# IRQF401RCT6.net
KiCad netlist of a schematic drawn in EAGLE
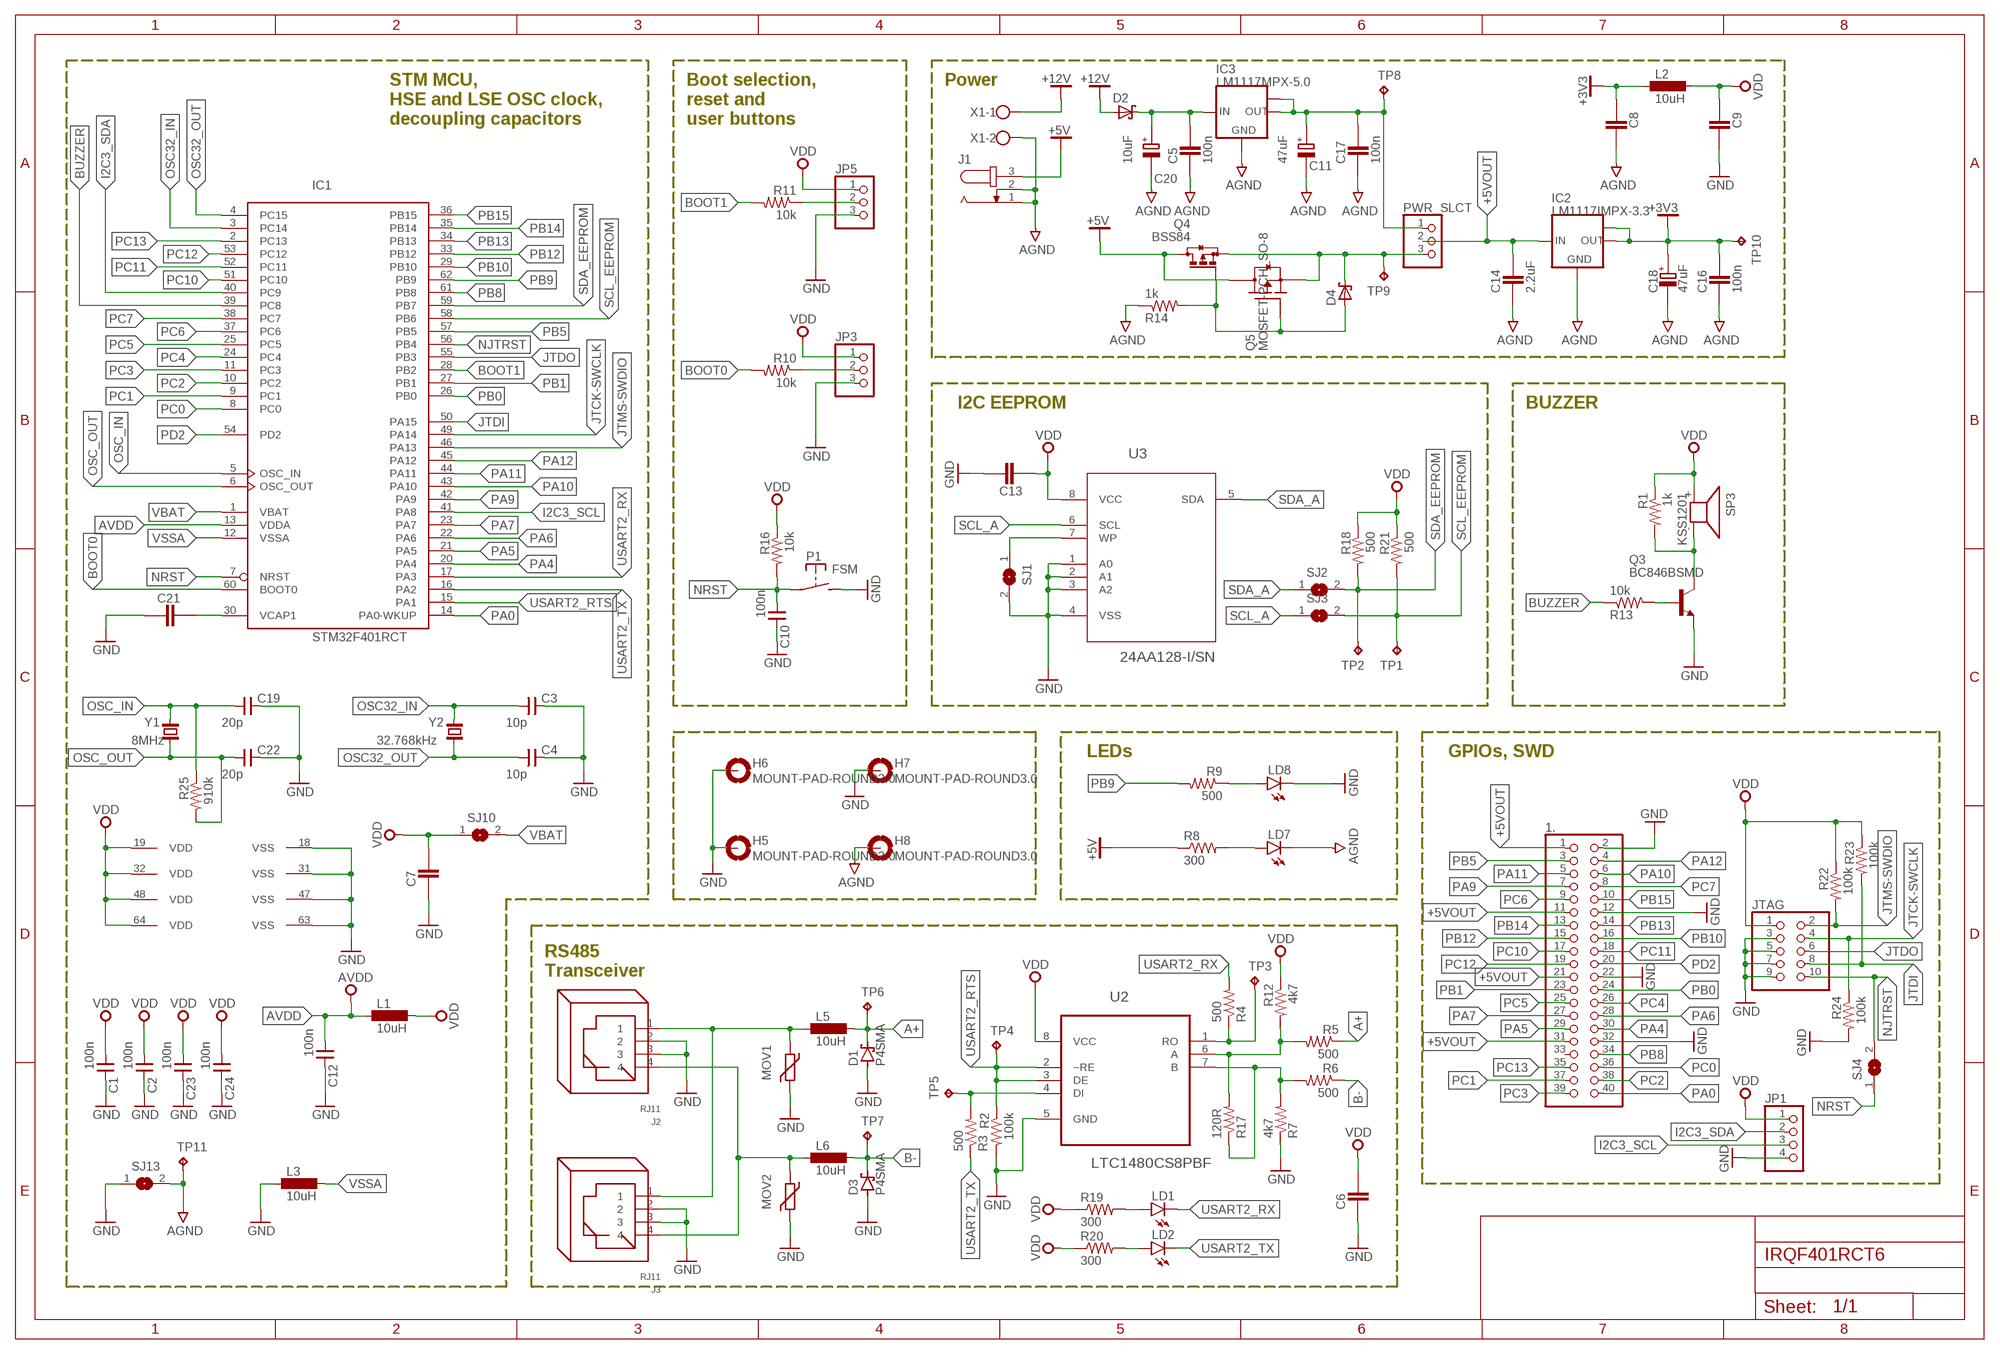
[diagram p0: schematic, sheet 1]

(export (version "E")
  (design (tool "Eeschema 10.0.6"))
  (components
    (comp (ref "1.")
      (value "PINHD-2X20")
      (footprint "eagle-import:2X20")
      (libsource (lib "eagle-import") (part "PINHD-2X20"))
    )
    (comp (ref "C1")
      (value "100n")
      (footprint "eagle-import:0805")
      (libsource (lib "eagle-import") (part "CNP-0805"))
    )
    (comp (ref "C2")
      (value "100n")
      (footprint "eagle-import:0805")
      (libsource (lib "eagle-import") (part "CNP-0805"))
    )
    (comp (ref "C3")
      (value "10p")
      (footprint "eagle-import:0805")
      (libsource (lib "eagle-import") (part "CNP-0805"))
    )
    (comp (ref "C4")
      (value "10p")
      (footprint "eagle-import:0805")
      (libsource (lib "eagle-import") (part "CNP-0805"))
    )
    (comp (ref "C5")
      (value "100n")
      (footprint "eagle-import:CAPC2012X145AN")
      (libsource (lib "eagle-import") (part "CAPACITOR_0805"))
    )
    (comp (ref "C6")
      (value "CAPACITOR_1206")
      (footprint "eagle-import:CAPC3215X168N")
      (libsource (lib "eagle-import") (part "CAPACITOR_1206"))
    )
    (comp (ref "C7")
      (value "CAPACITOR_1206")
      (footprint "eagle-import:CAPC3215X168N")
      (libsource (lib "eagle-import") (part "CAPACITOR_1206"))
    )
    (comp (ref "C8")
      (value "CAPACITOR_1206")
      (footprint "eagle-import:CAPC3215X168N")
      (libsource (lib "eagle-import") (part "CAPACITOR_1206"))
    )
    (comp (ref "C9")
      (value "CAPACITOR_1206")
      (footprint "eagle-import:CAPC3215X168N")
      (libsource (lib "eagle-import") (part "CAPACITOR_1206"))
    )
    (comp (ref "C10")
      (value "100n")
      (footprint "eagle-import:0805")
      (libsource (lib "eagle-import") (part "CNP-0805"))
    )
    (comp (ref "C11")
      (value "47uF")
      (footprint "eagle-import:CAPAE660X540N")
      (libsource (lib "eagle-import") (part "POLARISED_CASE_D"))
    )
    (comp (ref "C12")
      (value "100n")
      (footprint "eagle-import:0805")
      (libsource (lib "eagle-import") (part "CNP-0805"))
    )
    (comp (ref "C13")
      (value "CAPACITOR_1206")
      (footprint "eagle-import:CAPC3215X168N")
      (libsource (lib "eagle-import") (part "CAPACITOR_1206"))
    )
    (comp (ref "C14")
      (value "2.2uF")
      (footprint "eagle-import:CAPC3215X168N")
      (libsource (lib "eagle-import") (part "CAPACITOR_1206"))
    )
    (comp (ref "C16")
      (value "100n")
      (footprint "eagle-import:CAPC2012X145AN")
      (libsource (lib "eagle-import") (part "CAPACITOR_0805"))
    )
    (comp (ref "C17")
      (value "100n")
      (footprint "eagle-import:CAPC2012X145AN")
      (libsource (lib "eagle-import") (part "CAPACITOR_0805"))
    )
    (comp (ref "C18")
      (value "47uF")
      (footprint "eagle-import:CAPAE530X540N")
      (libsource (lib "eagle-import") (part "POLARISED_CASE_C"))
    )
    (comp (ref "C19")
      (value "20p")
      (footprint "eagle-import:0805")
      (libsource (lib "eagle-import") (part "CNP-0805"))
    )
    (comp (ref "C20")
      (value "10uF")
      (footprint "eagle-import:CAPAE430X540N")
      (libsource (lib "eagle-import") (part "POLARISED_CASE_B"))
    )
    (comp (ref "C21")
      (value "CAPACITOR_1206")
      (footprint "eagle-import:CAPC3215X168N")
      (libsource (lib "eagle-import") (part "CAPACITOR_1206"))
    )
    (comp (ref "C22")
      (value "20p")
      (footprint "eagle-import:0805")
      (libsource (lib "eagle-import") (part "CNP-0805"))
    )
    (comp (ref "C23")
      (value "100n")
      (footprint "eagle-import:0805")
      (libsource (lib "eagle-import") (part "CNP-0805"))
    )
    (comp (ref "C24")
      (value "100n")
      (footprint "eagle-import:0805")
      (libsource (lib "eagle-import") (part "CNP-0805"))
    )
    (comp (ref "D1")
      (value "P4SMA")
      (footprint "eagle-import:SMB")
      (libsource (lib "eagle-import") (part "SCHOTTKY-DIODESMD"))
    )
    (comp (ref "D2")
      (value "SCHOTTKY_SMA")
      (footprint "eagle-import:DIOM5326X292N")
      (libsource (lib "eagle-import") (part "SCHOTTKY_SMA"))
    )
    (comp (ref "D3")
      (value "P4SMA")
      (footprint "eagle-import:SMB")
      (libsource (lib "eagle-import") (part "SCHOTTKY-DIODESMD"))
    )
    (comp (ref "D4")
      (value "SCHOTTKY_SMA")
      (footprint "eagle-import:DIOM5326X292N")
      (libsource (lib "eagle-import") (part "SCHOTTKY_SMA"))
    )
    (comp (ref "H5")
      (value "MOUNT-PAD-ROUND3.0")
      (footprint "eagle-import:3,0-PAD")
      (libsource (lib "eagle-import") (part "MOUNT-PAD-ROUND3.0"))
    )
    (comp (ref "H6")
      (value "MOUNT-PAD-ROUND3.0")
      (footprint "eagle-import:3,0-PAD")
      (libsource (lib "eagle-import") (part "MOUNT-PAD-ROUND3.0"))
    )
    (comp (ref "H7")
      (value "MOUNT-PAD-ROUND3.0")
      (footprint "eagle-import:3,0-PAD")
      (libsource (lib "eagle-import") (part "MOUNT-PAD-ROUND3.0"))
    )
    (comp (ref "H8")
      (value "MOUNT-PAD-ROUND3.0")
      (footprint "eagle-import:3,0-PAD")
      (libsource (lib "eagle-import") (part "MOUNT-PAD-ROUND3.0"))
    )
    (comp (ref "IC1")
      (value "STM32F401RCT")
      (footprint "eagle-import:LQFP64")
      (libsource (lib "eagle-import") (part "STM32F401RTC"))
    )
    (comp (ref "IC2")
      (value "LM1117IMPX-3.3")
      (footprint "eagle-import:SOT223")
      (libsource (lib "eagle-import") (part "LM1117IMPX-3.3"))
    )
    (comp (ref "IC3")
      (value "LM1117MPX-5.0")
      (footprint "eagle-import:SOT223")
      (libsource (lib "eagle-import") (part "LM1117MPX-5.0"))
    )
    (comp (ref "J1")
      (value "JACK-PLUG1")
      (footprint "eagle-import:SPC4078")
      (libsource (lib "eagle-import") (part "JACK-PLUG1"))
    )
    (comp (ref "J2")
      (value "RJ11")
      (footprint "eagle-import:RJ11")
      (libsource (lib "eagle-import") (part "RJ11"))
    )
    (comp (ref "J3")
      (value "RJ11")
      (footprint "eagle-import:RJ11")
      (libsource (lib "eagle-import") (part "RJ11"))
    )
    (comp (ref "JP1")
      (value "PINHD-1X4")
      (footprint "eagle-import:1X04")
      (libsource (lib "eagle-import") (part "PINHD-1X4"))
    )
    (comp (ref "JP3")
      (value "PINHD-1X3")
      (footprint "eagle-import:1X03")
      (libsource (lib "eagle-import") (part "PINHD-1X3"))
    )
    (comp (ref "JP5")
      (value "PINHD-1X3")
      (footprint "eagle-import:1X03")
      (libsource (lib "eagle-import") (part "PINHD-1X3"))
    )
    (comp (ref "JTAG")
      (value "PINHD-2X5")
      (footprint "eagle-import:2X05")
      (libsource (lib "eagle-import") (part "PINHD-2X5"))
    )
    (comp (ref "L1")
      (value "10uH")
      (footprint "eagle-import:INDC1608X95N")
      (libsource (lib "eagle-import") (part "INDUCTOR_0603"))
    )
    (comp (ref "L2")
      (value "10uH")
      (footprint "eagle-import:INDC1608X95N")
      (libsource (lib "eagle-import") (part "INDUCTOR_0603"))
    )
    (comp (ref "L3")
      (value "10uH")
      (footprint "eagle-import:INDC1608X95N")
      (libsource (lib "eagle-import") (part "INDUCTOR_0603"))
    )
    (comp (ref "L5")
      (value "10uH")
      (footprint "eagle-import:INDC1608X95N")
      (libsource (lib "eagle-import") (part "INDUCTOR_0603"))
    )
    (comp (ref "L6")
      (value "10uH")
      (footprint "eagle-import:INDC1608X95N")
      (libsource (lib "eagle-import") (part "INDUCTOR_0603"))
    )
    (comp (ref "LD1")
      (value "LEDCHIPLED_0805")
      (footprint "eagle-import:CHIPLED_0805")
      (libsource (lib "eagle-import") (part "LEDCHIPLED_0805"))
    )
    (comp (ref "LD2")
      (value "LEDCHIPLED_0805")
      (footprint "eagle-import:CHIPLED_0805")
      (libsource (lib "eagle-import") (part "LEDCHIPLED_0805"))
    )
    (comp (ref "LD7")
      (value "LEDCHIPLED_0805")
      (footprint "eagle-import:CHIPLED_0805")
      (libsource (lib "eagle-import") (part "LEDCHIPLED_0805"))
    )
    (comp (ref "LD8")
      (value "LEDCHIPLED_0805")
      (footprint "eagle-import:CHIPLED_0805")
      (libsource (lib "eagle-import") (part "LEDCHIPLED_0805"))
    )
    (comp (ref "MOV1")
      (value "VARISTOR_0805")
      (footprint "eagle-import:VARC2012X70N")
      (libsource (lib "eagle-import") (part "VARISTOR_0805"))
    )
    (comp (ref "MOV2")
      (value "VARISTOR_0805")
      (footprint "eagle-import:VARC2012X70N")
      (libsource (lib "eagle-import") (part "VARISTOR_0805"))
    )
    (comp (ref "P1")
      (value "FSM")
      (footprint "eagle-import:FSM")
      (libsource (lib "eagle-import") (part "FSM"))
    )
    (comp (ref "PWR_SLCT")
      (value "PINHD-1X3")
      (footprint "eagle-import:1X03")
      (libsource (lib "eagle-import") (part "PINHD-1X3"))
    )
    (comp (ref "Q3")
      (value "BC846BSMD")
      (footprint "eagle-import:SOT23")
      (libsource (lib "eagle-import") (part "BC846SMDB"))
    )
    (comp (ref "Q4")
      (value "BSS84")
      (footprint "eagle-import:SOT23")
      (libsource (lib "eagle-import") (part "BSS84"))
    )
    (comp (ref "Q5")
      (value "MOSFET-PCH_SO-8")
      (footprint "eagle-import:SOIC127P600X175-8AN")
      (libsource (lib "eagle-import") (part "MOSFET-PCH_SO-8"))
    )
    (comp (ref "R1")
      (value "1k")
      (footprint "eagle-import:M0805")
      (libsource (lib "eagle-import") (part "R-US_M0805"))
    )
    (comp (ref "R2")
      (value "100k")
      (footprint "eagle-import:M0805")
      (libsource (lib "eagle-import") (part "R-US_M0805"))
    )
    (comp (ref "R3")
      (value "500")
      (footprint "eagle-import:M0805")
      (libsource (lib "eagle-import") (part "R-US_M0805"))
    )
    (comp (ref "R4")
      (value "500")
      (footprint "eagle-import:M0805")
      (libsource (lib "eagle-import") (part "R-US_M0805"))
    )
    (comp (ref "R5")
      (value "500")
      (footprint "eagle-import:M0805")
      (libsource (lib "eagle-import") (part "R-US_M0805"))
    )
    (comp (ref "R6")
      (value "500")
      (footprint "eagle-import:M0805")
      (libsource (lib "eagle-import") (part "R-US_M0805"))
    )
    (comp (ref "R7")
      (value "4k7")
      (footprint "eagle-import:M0805")
      (libsource (lib "eagle-import") (part "R-US_M0805"))
    )
    (comp (ref "R8")
      (value "300")
      (footprint "eagle-import:M0805")
      (libsource (lib "eagle-import") (part "R-US_M0805"))
    )
    (comp (ref "R9")
      (value "500")
      (footprint "eagle-import:M0805")
      (libsource (lib "eagle-import") (part "R-US_M0805"))
    )
    (comp (ref "R10")
      (value "10k")
      (footprint "eagle-import:M0805")
      (libsource (lib "eagle-import") (part "R-US_M0805"))
    )
    (comp (ref "R11")
      (value "10k")
      (footprint "eagle-import:M0805")
      (libsource (lib "eagle-import") (part "R-US_M0805"))
    )
    (comp (ref "R12")
      (value "4k7")
      (footprint "eagle-import:M0805")
      (libsource (lib "eagle-import") (part "R-US_M0805"))
    )
    (comp (ref "R13")
      (value "10k")
      (footprint "eagle-import:M0805")
      (libsource (lib "eagle-import") (part "R-US_M0805"))
    )
    (comp (ref "R14")
      (value "1k")
      (footprint "eagle-import:M0805")
      (libsource (lib "eagle-import") (part "R-US_M0805"))
    )
    (comp (ref "R16")
      (value "10k")
      (footprint "eagle-import:M0805")
      (libsource (lib "eagle-import") (part "R-US_M0805"))
    )
    (comp (ref "R17")
      (value "120R")
      (footprint "eagle-import:M0805")
      (libsource (lib "eagle-import") (part "R-US_M0805"))
    )
    (comp (ref "R18")
      (value "500")
      (footprint "eagle-import:M0805")
      (libsource (lib "eagle-import") (part "R-US_M0805"))
    )
    (comp (ref "R19")
      (value "300")
      (footprint "eagle-import:M0805")
      (libsource (lib "eagle-import") (part "R-US_M0805"))
    )
    (comp (ref "R20")
      (value "300")
      (footprint "eagle-import:M0805")
      (libsource (lib "eagle-import") (part "R-US_M0805"))
    )
    (comp (ref "R21")
      (value "500")
      (footprint "eagle-import:M0805")
      (libsource (lib "eagle-import") (part "R-US_M0805"))
    )
    (comp (ref "R22")
      (value "100k")
      (footprint "eagle-import:M0805")
      (libsource (lib "eagle-import") (part "R-US_M0805"))
    )
    (comp (ref "R23")
      (value "100k")
      (footprint "eagle-import:M0805")
      (libsource (lib "eagle-import") (part "R-US_M0805"))
    )
    (comp (ref "R24")
      (value "100k")
      (footprint "eagle-import:M0805")
      (libsource (lib "eagle-import") (part "R-US_M0805"))
    )
    (comp (ref "R25")
      (value "910k")
      (footprint "eagle-import:M0805")
      (libsource (lib "eagle-import") (part "R-US_M0805"))
    )
    (comp (ref "SJ1") (value "SJ") (footprint "eagle-import:SJ") (libsource (lib "eagle-import") (part "SJ")))
    (comp (ref "SJ2") (value "SJ") (footprint "eagle-import:SJ") (libsource (lib "eagle-import") (part "SJ")))
    (comp (ref "SJ3") (value "SJ") (footprint "eagle-import:SJ") (libsource (lib "eagle-import") (part "SJ")))
    (comp (ref "SJ4") (value "SJ") (footprint "eagle-import:SJ") (libsource (lib "eagle-import") (part "SJ")))
    (comp (ref "SJ10")
      (value "SJ")
      (footprint "eagle-import:SJ")
      (libsource (lib "eagle-import") (part "SJ"))
    )
    (comp (ref "SJ13")
      (value "SJ")
      (footprint "eagle-import:SJ")
      (libsource (lib "eagle-import") (part "SJ"))
    )
    (comp (ref "SP3")
      (value "KSS1201")
      (footprint "eagle-import:KSS1201")
      (libsource (lib "eagle-import") (part "KSS1201"))
    )
    (comp (ref "TP1")
      (value "TPTP10R")
      (footprint "eagle-import:TP10R")
      (libsource (lib "eagle-import") (part "TPTP10R"))
    )
    (comp (ref "TP2")
      (value "TPTP10R")
      (footprint "eagle-import:TP10R")
      (libsource (lib "eagle-import") (part "TPTP10R"))
    )
    (comp (ref "TP3")
      (value "TPTP10R")
      (footprint "eagle-import:TP10R")
      (libsource (lib "eagle-import") (part "TPTP10R"))
    )
    (comp (ref "TP4")
      (value "TPTP10R")
      (footprint "eagle-import:TP10R")
      (libsource (lib "eagle-import") (part "TPTP10R"))
    )
    (comp (ref "TP5")
      (value "TPTP10R")
      (footprint "eagle-import:TP10R")
      (libsource (lib "eagle-import") (part "TPTP10R"))
    )
    (comp (ref "TP6")
      (value "TPTP10R")
      (footprint "eagle-import:TP10R")
      (libsource (lib "eagle-import") (part "TPTP10R"))
    )
    (comp (ref "TP7")
      (value "TPTP10R")
      (footprint "eagle-import:TP10R")
      (libsource (lib "eagle-import") (part "TPTP10R"))
    )
    (comp (ref "TP8")
      (value "TPTP10R")
      (footprint "eagle-import:TP10R")
      (libsource (lib "eagle-import") (part "TPTP10R"))
    )
    (comp (ref "TP9")
      (value "TPTP10R")
      (footprint "eagle-import:TP10R")
      (libsource (lib "eagle-import") (part "TPTP10R"))
    )
    (comp (ref "TP10")
      (value "TPTP10R")
      (footprint "eagle-import:TP10R")
      (libsource (lib "eagle-import") (part "TPTP10R"))
    )
    (comp (ref "TP11")
      (value "TPTP10R")
      (footprint "eagle-import:TP10R")
      (libsource (lib "eagle-import") (part "TPTP10R"))
    )
    (comp (ref "U2")
      (value "LTC1480CS8PBF")
      (footprint "eagle-import:SOIC127P600X175-8N")
      (fields (field (name "MPN") "LTC1480CS8#PBF"))
      (libsource (lib "eagle-import") (part "LTC1480CS8PBF"))
    )
    (comp (ref "U3")
      (value "24AA128-I/SN")
      (footprint "eagle-import:SOIC127P600X175-8N")
      (libsource (lib "eagle-import") (part "24AA128-I/SN"))
    )
    (comp (ref "X1")
      (value "W237-102")
      (footprint "eagle-import:W237-102")
      (fields (field (name "MPN") "237-102"))
      (libsource (lib "eagle-import") (part "W237-102"))
    )
    (comp (ref "Y1")
      (value "8MHz")
      (footprint "eagle-import:HC49_S")
      (libsource (lib "eagle-import") (part "CRYTALHC49S"))
    )
    (comp (ref "Y2")
      (value "32.768kHz")
      (footprint "eagle-import:TC26H")
      (libsource (lib "eagle-import") (part "CRYTALTC26H"))
    )
  )
  (nets
    (net (code "1") (name "+3V3") (class "Default")
      (node (ref "C16") (pin "2") (pinfunction "2_2") (pintype "passive"))
      (node (ref "C18") (pin "+") (pinfunction "+_+") (pintype "passive"))
      (node (ref "C8") (pin "1") (pinfunction "1_1") (pintype "passive"))
      (node (ref "IC2") (pin "2") (pinfunction "OUT_2") (pintype "passive"))
      (node (ref "IC2") (pin "TAB") (pinfunction "OUT1_TAB") (pintype "passive"))
      (node (ref "L2") (pin "1") (pinfunction "1_1") (pintype "passive"))
      (node (ref "TP10") (pin "TP") (pinfunction "TP_TP") (pintype "input"))
    )
    (net (code "2") (name "+5V") (class "Default")
      (node (ref "J1") (pin "3") (pinfunction "3_3") (pintype "passive"))
      (node (ref "Q4") (pin "3") (pinfunction "D_3") (pintype "passive"))
      (node (ref "Q5") (pin "5") (pinfunction "D_5") (pintype "passive"))
      (node (ref "R8") (pin "1") (pinfunction "1_1") (pintype "passive"))
    )
    (net (code "3") (name "+5VOUT") (class "Default")
      (node (ref "1.") (pin "1") (pinfunction "1_1") (pintype "passive"))
      (node (ref "1.") (pin "11") (pinfunction "11_11") (pintype "passive"))
      (node (ref "1.") (pin "21") (pinfunction "21_21") (pintype "passive"))
      (node (ref "1.") (pin "31") (pinfunction "31_31") (pintype "passive"))
      (node (ref "C14") (pin "2") (pinfunction "2_2") (pintype "passive"))
      (node (ref "IC2") (pin "3") (pinfunction "IN_3") (pintype "input"))
      (node (ref "PWR_SLCT") (pin "2") (pinfunction "2_2") (pintype "passive"))
    )
    (net (code "4") (name "+12V") (class "Default")
      (node (ref "D2") (pin "A") (pinfunction "A_A") (pintype "passive"))
      (node (ref "X1") (pin "1") (pinfunction "KL_1") (pintype "passive"))
    )
    (net (code "5") (name "A+") (class "Default")
      (node (ref "D1") (pin "C") (pinfunction "C_C") (pintype "passive"))
      (node (ref "L5") (pin "2") (pinfunction "2_2") (pintype "passive"))
      (node (ref "R5") (pin "1") (pinfunction "1_1") (pintype "passive"))
      (node (ref "TP6") (pin "TP") (pinfunction "TP_TP") (pintype "input"))
    )
    (net (code "6") (name "AGND") (class "Default")
      (node (ref "C11") (pin "-") (pinfunction "-_-") (pintype "passive"))
      (node (ref "C14") (pin "1") (pinfunction "1_1") (pintype "passive"))
      (node (ref "C16") (pin "1") (pinfunction "1_1") (pintype "passive"))
      (node (ref "C17") (pin "1") (pinfunction "1_1") (pintype "passive"))
      (node (ref "C18") (pin "-") (pinfunction "-_-") (pintype "passive"))
      (node (ref "C20") (pin "-") (pinfunction "-_-") (pintype "passive"))
      (node (ref "C5") (pin "1") (pinfunction "1_1") (pintype "passive"))
      (node (ref "C8") (pin "2") (pinfunction "2_2") (pintype "passive"))
      (node (ref "H8") (pin "B3,0") (pinfunction "MOUNT_B3,0") (pintype "passive"))
      (node (ref "IC2") (pin "1") (pinfunction "GND_1") (pintype "input"))
      (node (ref "IC3") (pin "1") (pinfunction "GND_1") (pintype "input"))
      (node (ref "J1") (pin "1") (pinfunction "1_1") (pintype "passive"))
      (node (ref "J1") (pin "2") (pinfunction "2_2") (pintype "passive"))
      (node (ref "LD7") (pin "C") (pinfunction "C_C") (pintype "passive"))
      (node (ref "R14") (pin "1") (pinfunction "1_1") (pintype "passive"))
      (node (ref "SJ13") (pin "2") (pinfunction "2_2") (pintype "passive"))
      (node (ref "TP11") (pin "TP") (pinfunction "TP_TP") (pintype "input"))
      (node (ref "X1") (pin "2") (pinfunction "KL_2") (pintype "passive"))
    )
    (net (code "7") (name "AVDD") (class "Default")
      (node (ref "C12") (pin "1") (pinfunction "1_1") (pintype "passive"))
      (node (ref "IC1") (pin "13") (pinfunction "VDDA_13") (pintype "power_in"))
      (node (ref "L1") (pin "1") (pinfunction "1_1") (pintype "passive"))
    )
    (net (code "8") (name "B-") (class "Default")
      (node (ref "D3") (pin "C") (pinfunction "C_C") (pintype "passive"))
      (node (ref "L6") (pin "2") (pinfunction "2_2") (pintype "passive"))
      (node (ref "R6") (pin "1") (pinfunction "1_1") (pintype "passive"))
      (node (ref "TP7") (pin "TP") (pinfunction "TP_TP") (pintype "input"))
    )
    (net (code "9") (name "BOOT0") (class "Default")
      (node (ref "IC1") (pin "60") (pinfunction "BOOT0_60") (pintype "input"))
      (node (ref "R10") (pin "2") (pinfunction "2_2") (pintype "passive"))
    )
    (net (code "10") (name "BOOT1") (class "Default")
      (node (ref "IC1") (pin "28") (pinfunction "PB2_28") (pintype "bidirectional"))
      (node (ref "R11") (pin "2") (pinfunction "2_2") (pintype "passive"))
    )
    (net (code "11") (name "BUZZER") (class "Default")
      (node (ref "IC1") (pin "39") (pinfunction "PC8_39") (pintype "bidirectional"))
      (node (ref "R13") (pin "1") (pinfunction "1_1") (pintype "passive"))
    )
    (net (code "12") (name "GND") (class "Default")
      (node (ref "1.") (pin "12") (pinfunction "12_12") (pintype "passive"))
      (node (ref "1.") (pin "2") (pinfunction "2_2") (pintype "passive"))
      (node (ref "1.") (pin "22") (pinfunction "22_22") (pintype "passive"))
      (node (ref "1.") (pin "32") (pinfunction "32_32") (pintype "passive"))
      (node (ref "C1") (pin "2") (pinfunction "2_2") (pintype "passive"))
      (node (ref "C10") (pin "2") (pinfunction "2_2") (pintype "passive"))
      (node (ref "C12") (pin "2") (pinfunction "2_2") (pintype "passive"))
      (node (ref "C13") (pin "2") (pinfunction "2_2") (pintype "passive"))
      (node (ref "C19") (pin "2") (pinfunction "2_2") (pintype "passive"))
      (node (ref "C2") (pin "2") (pinfunction "2_2") (pintype "passive"))
      (node (ref "C21") (pin "1") (pinfunction "1_1") (pintype "passive"))
      (node (ref "C22") (pin "2") (pinfunction "2_2") (pintype "passive"))
      (node (ref "C23") (pin "2") (pinfunction "2_2") (pintype "passive"))
      (node (ref "C24") (pin "2") (pinfunction "2_2") (pintype "passive"))
      (node (ref "C3") (pin "2") (pinfunction "2_2") (pintype "passive"))
      (node (ref "C4") (pin "2") (pinfunction "2_2") (pintype "passive"))
      (node (ref "C6") (pin "1") (pinfunction "1_1") (pintype "passive"))
      (node (ref "C7") (pin "1") (pinfunction "1_1") (pintype "passive"))
      (node (ref "C9") (pin "2") (pinfunction "2_2") (pintype "passive"))
      (node (ref "D1") (pin "A") (pinfunction "A_A") (pintype "passive"))
      (node (ref "D3") (pin "A") (pinfunction "A_A") (pintype "passive"))
      (node (ref "H5") (pin "B3,0") (pinfunction "MOUNT_B3,0") (pintype "passive"))
      (node (ref "H6") (pin "B3,0") (pinfunction "MOUNT_B3,0") (pintype "passive"))
      (node (ref "H7") (pin "B3,0") (pinfunction "MOUNT_B3,0") (pintype "passive"))
      (node (ref "IC1") (pin "18") (pinfunction "VSS_18") (pintype "power_in"))
      (node (ref "IC1") (pin "31") (pinfunction "VSS_31") (pintype "power_in"))
      (node (ref "IC1") (pin "47") (pinfunction "VSS_47") (pintype "power_in"))
      (node (ref "IC1") (pin "63") (pinfunction "VSS_63") (pintype "power_in"))
      (node (ref "J2") (pin "2") (pinfunction "2_2") (pintype "bidirectional"))
      (node (ref "J2") (pin "3") (pinfunction "3_3") (pintype "bidirectional"))
      (node (ref "J3") (pin "2") (pinfunction "2_2") (pintype "bidirectional"))
      (node (ref "J3") (pin "3") (pinfunction "3_3") (pintype "bidirectional"))
      (node (ref "JP1") (pin "4") (pinfunction "4_4") (pintype "passive"))
      (node (ref "JP3") (pin "3") (pinfunction "3_3") (pintype "passive"))
      (node (ref "JP5") (pin "3") (pinfunction "3_3") (pintype "passive"))
      (node (ref "JTAG") (pin "3") (pinfunction "3_3") (pintype "passive"))
      (node (ref "JTAG") (pin "5") (pinfunction "5_5") (pintype "passive"))
      (node (ref "JTAG") (pin "7") (pinfunction "7_7") (pintype "passive"))
      (node (ref "JTAG") (pin "9") (pinfunction "9_9") (pintype "passive"))
      (node (ref "L3") (pin "1") (pinfunction "1_1") (pintype "passive"))
      (node (ref "LD8") (pin "C") (pinfunction "C_C") (pintype "passive"))
      (node (ref "MOV1") (pin "1") (pinfunction "1_1") (pintype "passive"))
      (node (ref "MOV2") (pin "1") (pinfunction "1_1") (pintype "passive"))
      (node (ref "P1") (pin "P$2") (pinfunction "S_P$2") (pintype "passive"))
      (node (ref "Q3") (pin "2") (pinfunction "E_2") (pintype "passive"))
      (node (ref "R2") (pin "2") (pinfunction "2_2") (pintype "passive"))
      (node (ref "R24") (pin "2") (pinfunction "2_2") (pintype "passive"))
      (node (ref "R7") (pin "1") (pinfunction "1_1") (pintype "passive"))
      (node (ref "SJ1") (pin "2") (pinfunction "2_2") (pintype "passive"))
      (node (ref "SJ13") (pin "1") (pinfunction "1_1") (pintype "passive"))
      (node (ref "U2") (pin "5") (pinfunction "GND_5") (pintype "passive"))
      (node (ref "U3") (pin "1") (pinfunction "A0_1") (pintype "input"))
      (node (ref "U3") (pin "2") (pinfunction "A1_2") (pintype "input"))
      (node (ref "U3") (pin "3") (pinfunction "A2_3") (pintype "input"))
      (node (ref "U3") (pin "4") (pinfunction "VSS_4") (pintype "power_in"))
    )
    (net (code "13") (name "I2C3_SCL") (class "Default")
      (node (ref "IC1") (pin "41") (pinfunction "PA8_41") (pintype "bidirectional"))
      (node (ref "JP1") (pin "3") (pinfunction "3_3") (pintype "passive"))
    )
    (net (code "14") (name "I2C3_SDA") (class "Default")
      (node (ref "IC1") (pin "40") (pinfunction "PC9_40") (pintype "bidirectional"))
      (node (ref "JP1") (pin "2") (pinfunction "2_2") (pintype "passive"))
    )
    (net (code "15") (name "JTCK-SWCLK") (class "Default")
      (node (ref "IC1") (pin "49") (pinfunction "PA14_49") (pintype "bidirectional"))
      (node (ref "JTAG") (pin "4") (pinfunction "4_4") (pintype "passive"))
      (node (ref "R24") (pin "1") (pinfunction "1_1") (pintype "passive"))
    )
    (net (code "16") (name "JTDI") (class "Default")
      (node (ref "IC1") (pin "50") (pinfunction "PA15_50") (pintype "bidirectional"))
      (node (ref "JTAG") (pin "8") (pinfunction "8_8") (pintype "passive"))
      (node (ref "R23") (pin "2") (pinfunction "2_2") (pintype "passive"))
    )
    (net (code "17") (name "JTDO") (class "Default")
      (node (ref "IC1") (pin "55") (pinfunction "PB3_55") (pintype "bidirectional"))
      (node (ref "JTAG") (pin "6") (pinfunction "6_6") (pintype "passive"))
    )
    (net (code "18") (name "JTMS-SWDIO") (class "Default")
      (node (ref "IC1") (pin "46") (pinfunction "PA13_46") (pintype "bidirectional"))
      (node (ref "JTAG") (pin "2") (pinfunction "2_2") (pintype "passive"))
      (node (ref "R22") (pin "2") (pinfunction "2_2") (pintype "passive"))
    )
    (net (code "19") (name "NJTRST") (class "Default")
      (node (ref "IC1") (pin "56") (pinfunction "PB4_56") (pintype "bidirectional"))
      (node (ref "JTAG") (pin "10") (pinfunction "10_10") (pintype "passive"))
      (node (ref "SJ4") (pin "2") (pinfunction "2_2") (pintype "passive"))
    )
    (net (code "20") (name "NRST") (class "Default")
      (node (ref "C10") (pin "1") (pinfunction "1_1") (pintype "passive"))
      (node (ref "IC1") (pin "7") (pinfunction "NRST_7") (pintype "bidirectional"))
      (node (ref "P1") (pin "P$1") (pinfunction "P_P$1") (pintype "passive"))
      (node (ref "R16") (pin "2") (pinfunction "2_2") (pintype "passive"))
      (node (ref "SJ4") (pin "1") (pinfunction "1_1") (pintype "passive"))
    )
    (net (code "21") (name "Net-(IC1A-VCAP1)") (class "Default")
      (node (ref "C21") (pin "2") (pinfunction "2_2") (pintype "passive"))
      (node (ref "IC1") (pin "30") (pinfunction "VCAP1_30") (pintype "power_in"))
    )
    (net (code "22") (name "Net-(IC3-IN)") (class "Default")
      (node (ref "C20") (pin "+") (pinfunction "+_+") (pintype "passive"))
      (node (ref "C5") (pin "2") (pinfunction "2_2") (pintype "passive"))
      (node (ref "D2") (pin "K") (pinfunction "K_K") (pintype "passive"))
      (node (ref "IC3") (pin "3") (pinfunction "IN_3") (pintype "input"))
    )
    (net (code "23") (name "Net-(IC3-OUT)") (class "Default")
      (node (ref "C11") (pin "+") (pinfunction "+_+") (pintype "passive"))
      (node (ref "C17") (pin "2") (pinfunction "2_2") (pintype "passive"))
      (node (ref "IC3") (pin "2") (pinfunction "OUT_2") (pintype "passive"))
      (node (ref "IC3") (pin "TAB") (pinfunction "OUT1_TAB") (pintype "passive"))
      (node (ref "PWR_SLCT") (pin "1") (pinfunction "1_1") (pintype "passive"))
      (node (ref "TP8") (pin "TP") (pinfunction "TP_TP") (pintype "input"))
    )
    (net (code "24") (name "Net-(J2-Pad1)") (class "Default")
      (node (ref "J2") (pin "1") (pinfunction "1_1") (pintype "bidirectional"))
      (node (ref "J3") (pin "1") (pinfunction "1_1") (pintype "bidirectional"))
      (node (ref "L5") (pin "1") (pinfunction "1_1") (pintype "passive"))
      (node (ref "MOV1") (pin "2") (pinfunction "2_2") (pintype "passive"))
    )
    (net (code "25") (name "Net-(J2-Pad4)") (class "Default")
      (node (ref "J2") (pin "4") (pinfunction "4_4") (pintype "bidirectional"))
      (node (ref "J3") (pin "4") (pinfunction "4_4") (pintype "bidirectional"))
      (node (ref "L6") (pin "1") (pinfunction "1_1") (pintype "passive"))
      (node (ref "MOV2") (pin "2") (pinfunction "2_2") (pintype "passive"))
    )
    (net (code "26") (name "Net-(JP3-Pad2)") (class "Default")
      (node (ref "JP3") (pin "2") (pinfunction "2_2") (pintype "passive"))
      (node (ref "R10") (pin "1") (pinfunction "1_1") (pintype "passive"))
    )
    (net (code "27") (name "Net-(JP5-Pad2)") (class "Default")
      (node (ref "JP5") (pin "2") (pinfunction "2_2") (pintype "passive"))
      (node (ref "R11") (pin "1") (pinfunction "1_1") (pintype "passive"))
    )
    (net (code "28") (name "Net-(LD1-PadA)") (class "Default")
      (node (ref "LD1") (pin "A") (pinfunction "A_A") (pintype "passive"))
      (node (ref "R19") (pin "2") (pinfunction "2_2") (pintype "passive"))
    )
    (net (code "29") (name "Net-(LD2-PadA)") (class "Default")
      (node (ref "LD2") (pin "A") (pinfunction "A_A") (pintype "passive"))
      (node (ref "R20") (pin "2") (pinfunction "2_2") (pintype "passive"))
    )
    (net (code "30") (name "Net-(LD7-PadA)") (class "Default")
      (node (ref "LD7") (pin "A") (pinfunction "A_A") (pintype "passive"))
      (node (ref "R8") (pin "2") (pinfunction "2_2") (pintype "passive"))
    )
    (net (code "31") (name "Net-(LD8-PadA)") (class "Default")
      (node (ref "LD8") (pin "A") (pinfunction "A_A") (pintype "passive"))
      (node (ref "R9") (pin "1") (pinfunction "1_1") (pintype "passive"))
    )
    (net (code "32") (name "Net-(Q3-B)") (class "Default")
      (node (ref "Q3") (pin "1") (pinfunction "B_1") (pintype "passive"))
      (node (ref "R13") (pin "2") (pinfunction "2_2") (pintype "passive"))
    )
    (net (code "33") (name "Net-(Q3-C)") (class "Default")
      (node (ref "Q3") (pin "3") (pinfunction "C_3") (pintype "passive"))
      (node (ref "R1") (pin "2") (pinfunction "2_2") (pintype "passive"))
      (node (ref "SP3") (pin "-") (pinfunction "2_-") (pintype "passive"))
    )
    (net (code "34") (name "Net-(Q4-G)") (class "Default")
      (node (ref "D4") (pin "A") (pinfunction "A_A") (pintype "passive"))
      (node (ref "Q4") (pin "1") (pinfunction "G_1") (pintype "passive"))
      (node (ref "Q5") (pin "4") (pinfunction "G_4") (pintype "passive"))
      (node (ref "R14") (pin "2") (pinfunction "2_2") (pintype "passive"))
    )
    (net (code "35") (name "Net-(Q4-S)") (class "Default")
      (node (ref "D4") (pin "K") (pinfunction "K_K") (pintype "passive"))
      (node (ref "PWR_SLCT") (pin "3") (pinfunction "3_3") (pintype "passive"))
      (node (ref "Q4") (pin "2") (pinfunction "S_2") (pintype "passive"))
      (node (ref "Q5") (pin "1") (pinfunction "S_1") (pintype "passive"))
      (node (ref "TP9") (pin "TP") (pinfunction "TP_TP") (pintype "input"))
    )
    (net (code "36") (name "Net-(U2-A)") (class "Default")
      (node (ref "R12") (pin "2") (pinfunction "2_2") (pintype "passive"))
      (node (ref "R17") (pin "2") (pinfunction "2_2") (pintype "passive"))
      (node (ref "R5") (pin "2") (pinfunction "2_2") (pintype "passive"))
      (node (ref "U2") (pin "6") (pinfunction "A_6") (pintype "bidirectional"))
    )
    (net (code "37") (name "Net-(U2-B)") (class "Default")
      (node (ref "R17") (pin "1") (pinfunction "1_1") (pintype "passive"))
      (node (ref "R6") (pin "2") (pinfunction "2_2") (pintype "passive"))
      (node (ref "R7") (pin "2") (pinfunction "2_2") (pintype "passive"))
      (node (ref "U2") (pin "7") (pinfunction "B_7") (pintype "bidirectional"))
    )
    (net (code "38") (name "Net-(U2-DI)") (class "Default")
      (node (ref "R3") (pin "2") (pinfunction "2_2") (pintype "passive"))
      (node (ref "TP5") (pin "TP") (pinfunction "TP_TP") (pintype "input"))
      (node (ref "U2") (pin "4") (pinfunction "DI_4") (pintype "input"))
    )
    (net (code "39") (name "Net-(U2-RO)") (class "Default")
      (node (ref "R4") (pin "1") (pinfunction "1_1") (pintype "passive"))
      (node (ref "TP3") (pin "TP") (pinfunction "TP_TP") (pintype "input"))
      (node (ref "U2") (pin "1") (pinfunction "RO_1") (pintype "output"))
    )
    (net (code "40") (name "Net-(U3-WP)") (class "Default")
      (node (ref "SJ1") (pin "1") (pinfunction "1_1") (pintype "passive"))
      (node (ref "U3") (pin "7") (pinfunction "WP_7") (pintype "input"))
    )
    (net (code "41") (name "OSC32_IN") (class "Default")
      (node (ref "C3") (pin "1") (pinfunction "1_1") (pintype "passive"))
      (node (ref "IC1") (pin "3") (pinfunction "PC14_3") (pintype "bidirectional"))
      (node (ref "Y2") (pin "2") (pinfunction "2_2") (pintype "passive"))
    )
    (net (code "42") (name "OSC32_OUT") (class "Default")
      (node (ref "C4") (pin "1") (pinfunction "1_1") (pintype "passive"))
      (node (ref "IC1") (pin "4") (pinfunction "PC15_4") (pintype "bidirectional"))
      (node (ref "Y2") (pin "1") (pinfunction "1_1") (pintype "passive"))
    )
    (net (code "43") (name "OSC_IN") (class "Default")
      (node (ref "C19") (pin "1") (pinfunction "1_1") (pintype "passive"))
      (node (ref "IC1") (pin "5") (pinfunction "OSC_IN_5") (pintype "bidirectional"))
      (node (ref "R25") (pin "1") (pinfunction "1_1") (pintype "passive"))
      (node (ref "Y1") (pin "2") (pinfunction "2_2") (pintype "passive"))
    )
    (net (code "44") (name "OSC_OUT") (class "Default")
      (node (ref "C22") (pin "1") (pinfunction "1_1") (pintype "passive"))
      (node (ref "IC1") (pin "6") (pinfunction "OSC_OUT_6") (pintype "bidirectional"))
      (node (ref "R25") (pin "2") (pinfunction "2_2") (pintype "passive"))
      (node (ref "Y1") (pin "1") (pinfunction "1_1") (pintype "passive"))
    )
    (net (code "45") (name "PA0") (class "Default")
      (node (ref "1.") (pin "40") (pinfunction "40_40") (pintype "passive"))
      (node (ref "IC1") (pin "14") (pinfunction "PA0-WKUP_14") (pintype "bidirectional"))
    )
    (net (code "46") (name "PA4") (class "Default")
      (node (ref "1.") (pin "30") (pinfunction "30_30") (pintype "passive"))
      (node (ref "IC1") (pin "20") (pinfunction "PA4_20") (pintype "bidirectional"))
    )
    (net (code "47") (name "PA5") (class "Default")
      (node (ref "1.") (pin "29") (pinfunction "29_29") (pintype "passive"))
      (node (ref "IC1") (pin "21") (pinfunction "PA5_21") (pintype "bidirectional"))
    )
    (net (code "48") (name "PA6") (class "Default")
      (node (ref "1.") (pin "28") (pinfunction "28_28") (pintype "passive"))
      (node (ref "IC1") (pin "22") (pinfunction "PA6_22") (pintype "bidirectional"))
    )
    (net (code "49") (name "PA7") (class "Default")
      (node (ref "1.") (pin "27") (pinfunction "27_27") (pintype "passive"))
      (node (ref "IC1") (pin "23") (pinfunction "PA7_23") (pintype "bidirectional"))
    )
    (net (code "50") (name "PA9") (class "Default")
      (node (ref "1.") (pin "7") (pinfunction "7_7") (pintype "passive"))
      (node (ref "IC1") (pin "42") (pinfunction "PA9_42") (pintype "bidirectional"))
    )
    (net (code "51") (name "PA10") (class "Default")
      (node (ref "1.") (pin "6") (pinfunction "6_6") (pintype "passive"))
      (node (ref "IC1") (pin "43") (pinfunction "PA10_43") (pintype "bidirectional"))
    )
    (net (code "52") (name "PA11") (class "Default")
      (node (ref "1.") (pin "5") (pinfunction "5_5") (pintype "passive"))
      (node (ref "IC1") (pin "44") (pinfunction "PA11_44") (pintype "bidirectional"))
    )
    (net (code "53") (name "PA12") (class "Default")
      (node (ref "1.") (pin "4") (pinfunction "4_4") (pintype "passive"))
      (node (ref "IC1") (pin "45") (pinfunction "PA12_45") (pintype "bidirectional"))
    )
    (net (code "54") (name "PB0") (class "Default")
      (node (ref "1.") (pin "24") (pinfunction "24_24") (pintype "passive"))
      (node (ref "IC1") (pin "26") (pinfunction "PB0_26") (pintype "bidirectional"))
    )
    (net (code "55") (name "PB1") (class "Default")
      (node (ref "1.") (pin "23") (pinfunction "23_23") (pintype "passive"))
      (node (ref "IC1") (pin "27") (pinfunction "PB1_27") (pintype "bidirectional"))
    )
    (net (code "56") (name "PB5") (class "Default")
      (node (ref "1.") (pin "3") (pinfunction "3_3") (pintype "passive"))
      (node (ref "IC1") (pin "57") (pinfunction "PB5_57") (pintype "bidirectional"))
    )
    (net (code "57") (name "PB8") (class "Default")
      (node (ref "1.") (pin "34") (pinfunction "34_34") (pintype "passive"))
      (node (ref "IC1") (pin "61") (pinfunction "PB8_61") (pintype "bidirectional"))
    )
    (net (code "58") (name "PB9") (class "Default")
      (node (ref "IC1") (pin "62") (pinfunction "PB9_62") (pintype "bidirectional"))
      (node (ref "R9") (pin "2") (pinfunction "2_2") (pintype "passive"))
    )
    (net (code "59") (name "PB10") (class "Default")
      (node (ref "1.") (pin "16") (pinfunction "16_16") (pintype "passive"))
      (node (ref "IC1") (pin "29") (pinfunction "PB10_29") (pintype "bidirectional"))
    )
    (net (code "60") (name "PB12") (class "Default")
      (node (ref "1.") (pin "15") (pinfunction "15_15") (pintype "passive"))
      (node (ref "IC1") (pin "33") (pinfunction "PB12_33") (pintype "bidirectional"))
    )
    (net (code "61") (name "PB13") (class "Default")
      (node (ref "1.") (pin "14") (pinfunction "14_14") (pintype "passive"))
      (node (ref "IC1") (pin "34") (pinfunction "PB13_34") (pintype "bidirectional"))
    )
    (net (code "62") (name "PB14") (class "Default")
      (node (ref "1.") (pin "13") (pinfunction "13_13") (pintype "passive"))
      (node (ref "IC1") (pin "35") (pinfunction "PB14_35") (pintype "bidirectional"))
    )
    (net (code "63") (name "PB15") (class "Default")
      (node (ref "1.") (pin "10") (pinfunction "10_10") (pintype "passive"))
      (node (ref "IC1") (pin "36") (pinfunction "PB15_36") (pintype "bidirectional"))
    )
    (net (code "64") (name "PC0") (class "Default")
      (node (ref "1.") (pin "36") (pinfunction "36_36") (pintype "passive"))
      (node (ref "IC1") (pin "8") (pinfunction "PC0_8") (pintype "bidirectional"))
    )
    (net (code "65") (name "PC1") (class "Default")
      (node (ref "1.") (pin "37") (pinfunction "37_37") (pintype "passive"))
      (node (ref "IC1") (pin "9") (pinfunction "PC1_9") (pintype "bidirectional"))
    )
    (net (code "66") (name "PC2") (class "Default")
      (node (ref "1.") (pin "38") (pinfunction "38_38") (pintype "passive"))
      (node (ref "IC1") (pin "10") (pinfunction "PC2_10") (pintype "bidirectional"))
    )
    (net (code "67") (name "PC3") (class "Default")
      (node (ref "1.") (pin "39") (pinfunction "39_39") (pintype "passive"))
      (node (ref "IC1") (pin "11") (pinfunction "PC3_11") (pintype "bidirectional"))
    )
    (net (code "68") (name "PC4") (class "Default")
      (node (ref "1.") (pin "26") (pinfunction "26_26") (pintype "passive"))
      (node (ref "IC1") (pin "24") (pinfunction "PC4_24") (pintype "bidirectional"))
    )
    (net (code "69") (name "PC5") (class "Default")
      (node (ref "1.") (pin "25") (pinfunction "25_25") (pintype "passive"))
      (node (ref "IC1") (pin "25") (pinfunction "PC5_25") (pintype "bidirectional"))
    )
    (net (code "70") (name "PC6") (class "Default")
      (node (ref "1.") (pin "9") (pinfunction "9_9") (pintype "passive"))
      (node (ref "IC1") (pin "37") (pinfunction "PC6_37") (pintype "bidirectional"))
    )
    (net (code "71") (name "PC7") (class "Default")
      (node (ref "1.") (pin "8") (pinfunction "8_8") (pintype "passive"))
      (node (ref "IC1") (pin "38") (pinfunction "PC7_38") (pintype "bidirectional"))
    )
    (net (code "72") (name "PC10") (class "Default")
      (node (ref "1.") (pin "17") (pinfunction "17_17") (pintype "passive"))
      (node (ref "IC1") (pin "51") (pinfunction "PC10_51") (pintype "bidirectional"))
    )
    (net (code "73") (name "PC11") (class "Default")
      (node (ref "1.") (pin "18") (pinfunction "18_18") (pintype "passive"))
      (node (ref "IC1") (pin "52") (pinfunction "PC11_52") (pintype "bidirectional"))
    )
    (net (code "74") (name "PC12") (class "Default")
      (node (ref "1.") (pin "19") (pinfunction "19_19") (pintype "passive"))
      (node (ref "IC1") (pin "53") (pinfunction "PC12_53") (pintype "bidirectional"))
    )
    (net (code "75") (name "PC13") (class "Default")
      (node (ref "1.") (pin "35") (pinfunction "35_35") (pintype "passive"))
      (node (ref "IC1") (pin "2") (pinfunction "PC13_2") (pintype "bidirectional"))
    )
    (net (code "76") (name "PD2") (class "Default")
      (node (ref "1.") (pin "20") (pinfunction "20_20") (pintype "passive"))
      (node (ref "IC1") (pin "54") (pinfunction "PD2_54") (pintype "bidirectional"))
    )
    (net (code "77") (name "SCL_A") (class "Default")
      (node (ref "SJ3") (pin "1") (pinfunction "1_1") (pintype "passive"))
      (node (ref "U3") (pin "6") (pinfunction "SCL_6") (pintype "input"))
    )
    (net (code "78") (name "SCL_EEPROM") (class "Default")
      (node (ref "IC1") (pin "58") (pinfunction "PB6_58") (pintype "bidirectional"))
      (node (ref "R21") (pin "2") (pinfunction "2_2") (pintype "passive"))
      (node (ref "SJ3") (pin "2") (pinfunction "2_2") (pintype "passive"))
      (node (ref "TP1") (pin "TP") (pinfunction "TP_TP") (pintype "input"))
    )
    (net (code "79") (name "SDA_A") (class "Default")
      (node (ref "SJ2") (pin "1") (pinfunction "1_1") (pintype "passive"))
      (node (ref "U3") (pin "5") (pinfunction "SDA_5") (pintype "bidirectional"))
    )
    (net (code "80") (name "SDA_EEPROM") (class "Default")
      (node (ref "IC1") (pin "59") (pinfunction "PB7_59") (pintype "bidirectional"))
      (node (ref "R18") (pin "2") (pinfunction "2_2") (pintype "passive"))
      (node (ref "SJ2") (pin "2") (pinfunction "2_2") (pintype "passive"))
      (node (ref "TP2") (pin "TP") (pinfunction "TP_TP") (pintype "input"))
    )
    (net (code "81") (name "USART2_RTS") (class "Default")
      (node (ref "IC1") (pin "15") (pinfunction "PA1_15") (pintype "bidirectional"))
      (node (ref "R2") (pin "1") (pinfunction "1_1") (pintype "passive"))
      (node (ref "TP4") (pin "TP") (pinfunction "TP_TP") (pintype "input"))
      (node (ref "U2") (pin "2") (pinfunction "~{RE}_2") (pintype "input"))
      (node (ref "U2") (pin "3") (pinfunction "DE_3") (pintype "input"))
    )
    (net (code "82") (name "USART2_RX") (class "Default")
      (node (ref "IC1") (pin "17") (pinfunction "PA3_17") (pintype "bidirectional"))
      (node (ref "LD1") (pin "C") (pinfunction "C_C") (pintype "passive"))
      (node (ref "R4") (pin "2") (pinfunction "2_2") (pintype "passive"))
    )
    (net (code "83") (name "USART2_TX") (class "Default")
      (node (ref "IC1") (pin "16") (pinfunction "PA2_16") (pintype "bidirectional"))
      (node (ref "LD2") (pin "C") (pinfunction "C_C") (pintype "passive"))
      (node (ref "R3") (pin "1") (pinfunction "1_1") (pintype "passive"))
    )
    (net (code "84") (name "VBAT") (class "Default")
      (node (ref "IC1") (pin "1") (pinfunction "VBAT_1") (pintype "power_in"))
      (node (ref "SJ10") (pin "2") (pinfunction "2_2") (pintype "passive"))
    )
    (net (code "85") (name "VDD") (class "Default")
      (node (ref "C1") (pin "1") (pinfunction "1_1") (pintype "passive"))
      (node (ref "C13") (pin "1") (pinfunction "1_1") (pintype "passive"))
      (node (ref "C2") (pin "1") (pinfunction "1_1") (pintype "passive"))
      (node (ref "C23") (pin "1") (pinfunction "1_1") (pintype "passive"))
      (node (ref "C24") (pin "1") (pinfunction "1_1") (pintype "passive"))
      (node (ref "C6") (pin "2") (pinfunction "2_2") (pintype "passive"))
      (node (ref "C7") (pin "2") (pinfunction "2_2") (pintype "passive"))
      (node (ref "C9") (pin "1") (pinfunction "1_1") (pintype "passive"))
      (node (ref "IC1") (pin "19") (pinfunction "VDD_19") (pintype "power_in"))
      (node (ref "IC1") (pin "32") (pinfunction "VDD_32") (pintype "power_in"))
      (node (ref "IC1") (pin "48") (pinfunction "VDD_48") (pintype "power_in"))
      (node (ref "IC1") (pin "64") (pinfunction "VDD_64") (pintype "power_in"))
      (node (ref "JP1") (pin "1") (pinfunction "1_1") (pintype "passive"))
      (node (ref "JP3") (pin "1") (pinfunction "1_1") (pintype "passive"))
      (node (ref "JP5") (pin "1") (pinfunction "1_1") (pintype "passive"))
      (node (ref "JTAG") (pin "1") (pinfunction "1_1") (pintype "passive"))
      (node (ref "L1") (pin "2") (pinfunction "2_2") (pintype "passive"))
      (node (ref "L2") (pin "2") (pinfunction "2_2") (pintype "passive"))
      (node (ref "R1") (pin "1") (pinfunction "1_1") (pintype "passive"))
      (node (ref "R12") (pin "1") (pinfunction "1_1") (pintype "passive"))
      (node (ref "R16") (pin "1") (pinfunction "1_1") (pintype "passive"))
      (node (ref "R18") (pin "1") (pinfunction "1_1") (pintype "passive"))
      (node (ref "R19") (pin "1") (pinfunction "1_1") (pintype "passive"))
      (node (ref "R20") (pin "1") (pinfunction "1_1") (pintype "passive"))
      (node (ref "R21") (pin "1") (pinfunction "1_1") (pintype "passive"))
      (node (ref "R22") (pin "1") (pinfunction "1_1") (pintype "passive"))
      (node (ref "R23") (pin "1") (pinfunction "1_1") (pintype "passive"))
      (node (ref "SJ10") (pin "1") (pinfunction "1_1") (pintype "passive"))
      (node (ref "SP3") (pin "+") (pinfunction "1_+") (pintype "passive"))
      (node (ref "U2") (pin "8") (pinfunction "VCC_8") (pintype "power_in"))
      (node (ref "U3") (pin "8") (pinfunction "VCC_8") (pintype "power_in"))
    )
    (net (code "86") (name "VSSA") (class "Default")
      (node (ref "IC1") (pin "12") (pinfunction "VSSA_12") (pintype "power_in"))
      (node (ref "L3") (pin "2") (pinfunction "2_2") (pintype "passive"))
    )
    (net (code "87") (name "unconnected-(1.-Pad33)") (class "Default")
      (node (ref "1.") (pin "33") (pinfunction "33_33") (pintype "passive"))
    )
  )
)
